# mv-scheme.net
KiCad netlist of a schematic drawn in EAGLE
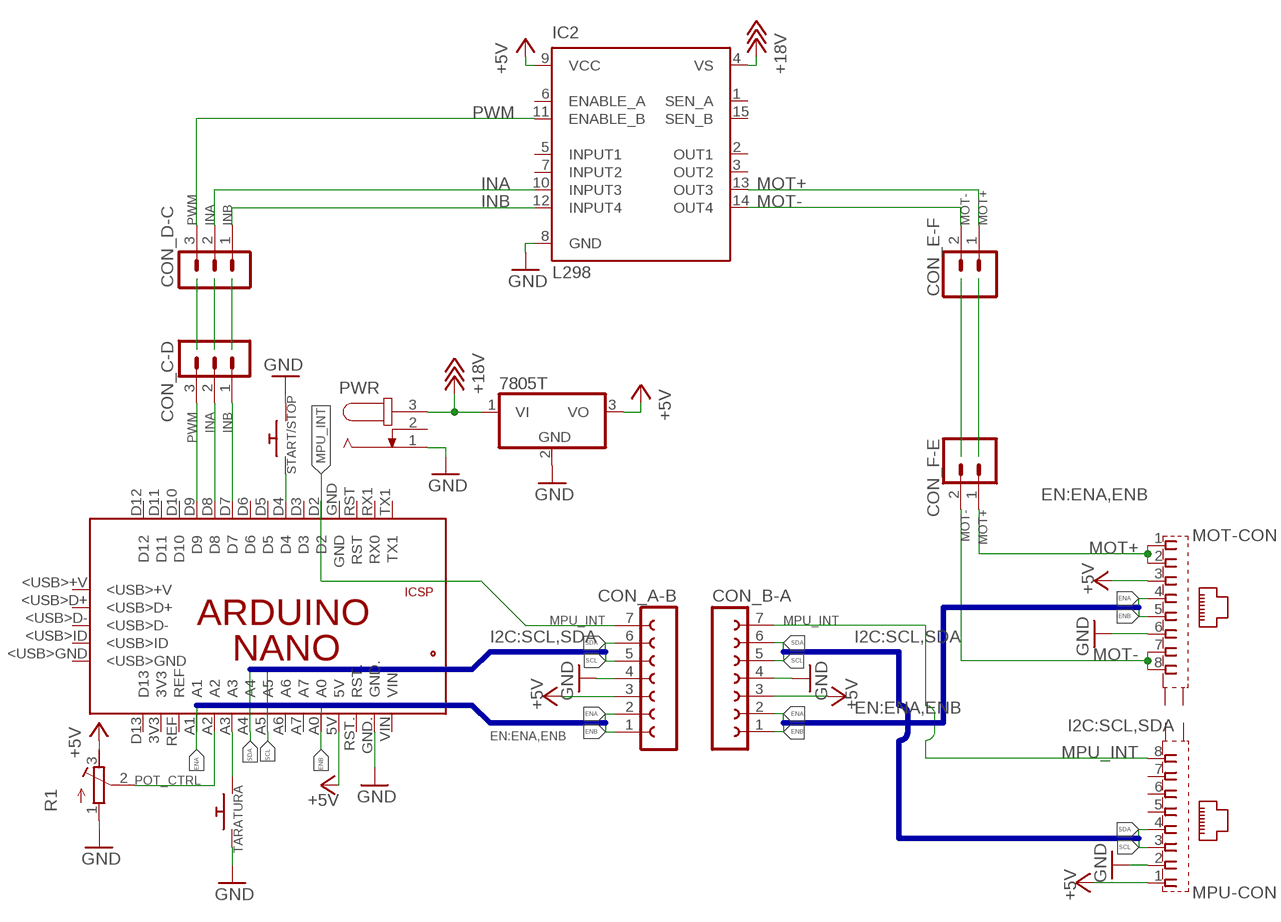
[diagram p0: schematic, sheet 1]

(export (version "E")
  (design (tool "Eeschema 10.0.6"))
  (components
    (comp (ref "CON_A-B")
      (value "FE07W")
      (footprint "eagle-import:FE07W")
      (libsource (lib "eagle-import") (part "FE07W"))
    )
    (comp (ref "CON_B-A")
      (value "FE07W")
      (footprint "eagle-import:FE07W")
      (libsource (lib "eagle-import") (part "FE07W"))
    )
    (comp (ref "CON_C-D")
      (value "MA03-1")
      (footprint "eagle-import:MA03-1")
      (libsource (lib "eagle-import") (part "MA03-1"))
    )
    (comp (ref "CON_D-C")
      (value "MA03-1")
      (footprint "eagle-import:MA03-1")
      (libsource (lib "eagle-import") (part "MA03-1"))
    )
    (comp (ref "CON_E-F")
      (value "CONN_02")
      (footprint "eagle-import:1X02")
      (libsource (lib "eagle-import") (part "CONN_02"))
    )
    (comp (ref "CON_F-E")
      (value "CONN_02")
      (footprint "eagle-import:1X02")
      (libsource (lib "eagle-import") (part "CONN_02"))
    )
    (comp (ref "IC1")
      (value "7805T")
      (footprint "eagle-import:TO220H")
      (libsource (lib "eagle-import") (part "78T05"))
    )
    (comp (ref "IC2")
      (value "L298")
      (footprint "eagle-import:MULTIWATT-15")
      (fields (field (name "MPN") "L298N"))
      (libsource (lib "eagle-import") (part "L298"))
    )
    (comp (ref "MOT-CON")
      (value "GLX-S-88M")
      (footprint "eagle-import:GLX-S-88M")
      (libsource (lib "eagle-import") (part "GLX-S-88M"))
    )
    (comp (ref "MPU-CON")
      (value "GLX-S-88M")
      (footprint "eagle-import:GLX-S-88M")
      (libsource (lib "eagle-import") (part "GLX-S-88M"))
    )
    (comp (ref "PCB1")
      (value "ARDUINO_NANO")
      (footprint "eagle-import:ARDUINO_NANO")
      (libsource (lib "eagle-import") (part "ARDUINO_NANO"))
    )
    (comp (ref "PWR")
      (value "JACK-PLUG1")
      (footprint "eagle-import:SPC4078")
      (libsource (lib "eagle-import") (part "JACK-PLUG1"))
    )
    (comp (ref "R1")
      (value "R-TRIMM64W")
      (footprint "eagle-import:RTRIM64W")
      (libsource (lib "eagle-import") (part "R-TRIMM64W"))
    )
    (comp (ref "START/STOP")
      (value "SWITCH_PUSHBUTTONEVQ-PE")
      (footprint "eagle-import:TACT_PANA-EVQ")
      (libsource (lib "eagle-import") (part "SWITCH_PUSHBUTTONEVQ-PE"))
    )
    (comp (ref "TARATURA")
      (value "SWITCH_PUSHBUTTONEVQ-PE")
      (footprint "eagle-import:TACT_PANA-EVQ")
      (libsource (lib "eagle-import") (part "SWITCH_PUSHBUTTONEVQ-PE"))
    )
  )
  (nets
    (net (code "3") (name "+5V") (class "Default")
      (node (ref "CON_A-B") (pin "3") (pinfunction "3_3") (pintype "passive"))
      (node (ref "CON_B-A") (pin "3") (pinfunction "3_3") (pintype "passive"))
      (node (ref "IC1") (pin "3") (pinfunction "VO_3") (pintype "passive"))
      (node (ref "IC2") (pin "9") (pinfunction "VCC_9") (pintype "power_in"))
      (node (ref "MOT-CON") (pin "3") (pinfunction "3_3") (pintype "passive"))
      (node (ref "MPU-CON") (pin "1") (pinfunction "1_1") (pintype "passive"))
      (node (ref "PCB1") (pin "5V") (pinfunction "5V_5V") (pintype "bidirectional"))
      (node (ref "R1") (pin "3") (pinfunction "E_3") (pintype "passive"))
    )
    (net (code "4") (name "+18V") (class "Default")
      (node (ref "IC1") (pin "1") (pinfunction "VI_1") (pintype "input"))
      (node (ref "IC2") (pin "4") (pinfunction "VS_4") (pintype "power_in"))
      (node (ref "PWR") (pin "3") (pinfunction "3_3") (pintype "passive"))
    )
    (net (code "5") (name "/INA") (class "Default")
      (node (ref "CON_C-D") (pin "2") (pinfunction "2_2") (pintype "passive"))
      (node (ref "CON_D-C") (pin "2") (pinfunction "2_2") (pintype "passive"))
      (node (ref "IC2") (pin "10") (pinfunction "INPUT3_10") (pintype "input"))
      (node (ref "PCB1") (pin "D8") (pinfunction "D8_D8") (pintype "bidirectional"))
    )
    (net (code "6") (name "/INB") (class "Default")
      (node (ref "CON_C-D") (pin "1") (pinfunction "1_1") (pintype "passive"))
      (node (ref "CON_D-C") (pin "1") (pinfunction "1_1") (pintype "passive"))
      (node (ref "IC2") (pin "12") (pinfunction "INPUT4_12") (pintype "input"))
      (node (ref "PCB1") (pin "D7") (pinfunction "D7_D7") (pintype "bidirectional"))
    )
    (net (code "7") (name "/MOT+") (class "Default")
      (node (ref "CON_E-F") (pin "1") (pinfunction "1_1") (pintype "passive"))
      (node (ref "CON_F-E") (pin "1") (pinfunction "1_1") (pintype "passive"))
      (node (ref "IC2") (pin "13") (pinfunction "OUT3_13") (pintype "output"))
      (node (ref "MOT-CON") (pin "1") (pinfunction "1_1") (pintype "passive"))
      (node (ref "MOT-CON") (pin "2") (pinfunction "2_2") (pintype "passive"))
    )
    (net (code "8") (name "/MOT-") (class "Default")
      (node (ref "CON_E-F") (pin "2") (pinfunction "2_2") (pintype "passive"))
      (node (ref "CON_F-E") (pin "2") (pinfunction "2_2") (pintype "passive"))
      (node (ref "IC2") (pin "14") (pinfunction "OUT4_14") (pintype "output"))
      (node (ref "MOT-CON") (pin "7") (pinfunction "7_7") (pintype "passive"))
      (node (ref "MOT-CON") (pin "8") (pinfunction "8_8") (pintype "passive"))
    )
    (net (code "9") (name "/POT_CTRL") (class "Default")
      (node (ref "PCB1") (pin "A2") (pinfunction "A2_A2") (pintype "bidirectional"))
      (node (ref "R1") (pin "2") (pinfunction "S_2") (pintype "passive"))
    )
    (net (code "10") (name "/PWM") (class "Default")
      (node (ref "CON_C-D") (pin "3") (pinfunction "3_3") (pintype "passive"))
      (node (ref "CON_D-C") (pin "3") (pinfunction "3_3") (pintype "passive"))
      (node (ref "IC2") (pin "11") (pinfunction "ENABLE_B_11") (pintype "input"))
      (node (ref "PCB1") (pin "D9") (pinfunction "D9_D9") (pintype "bidirectional"))
    )
    (net (code "13") (name "ENA") (class "Default")
      (node (ref "CON_A-B") (pin "2") (pinfunction "2_2") (pintype "passive"))
      (node (ref "CON_B-A") (pin "2") (pinfunction "2_2") (pintype "passive"))
      (node (ref "MOT-CON") (pin "4") (pinfunction "4_4") (pintype "passive"))
      (node (ref "PCB1") (pin "A1") (pinfunction "A1_A1") (pintype "bidirectional"))
    )
    (net (code "14") (name "ENB") (class "Default")
      (node (ref "CON_A-B") (pin "1") (pinfunction "1_1") (pintype "passive"))
      (node (ref "CON_B-A") (pin "1") (pinfunction "1_1") (pintype "passive"))
      (node (ref "MOT-CON") (pin "5") (pinfunction "5_5") (pintype "passive"))
      (node (ref "PCB1") (pin "A0") (pinfunction "A0_A0") (pintype "bidirectional"))
    )
    (net (code "15") (name "GND") (class "Default")
      (node (ref "CON_A-B") (pin "4") (pinfunction "4_4") (pintype "passive"))
      (node (ref "CON_B-A") (pin "4") (pinfunction "4_4") (pintype "passive"))
      (node (ref "IC1") (pin "2") (pinfunction "GND_2") (pintype "passive"))
      (node (ref "IC2") (pin "8") (pinfunction "GND_8") (pintype "power_in"))
      (node (ref "MOT-CON") (pin "6") (pinfunction "6_6") (pintype "passive"))
      (node (ref "MPU-CON") (pin "2") (pinfunction "2_2") (pintype "passive"))
      (node (ref "PCB1") (pin "GND.") (pinfunction "GND._GND.") (pintype "bidirectional"))
      (node (ref "PWR") (pin "1") (pinfunction "1_1") (pintype "passive"))
      (node (ref "R1") (pin "1") (pinfunction "A_1") (pintype "passive"))
      (node (ref "START/STOP") (pin "P$2") (pinfunction "P$2_P$2") (pintype "passive"))
      (node (ref "TARATURA") (pin "P$2") (pinfunction "P$2_P$2") (pintype "passive"))
    )
    (net (code "16") (name "MPU_INT") (class "Default")
      (node (ref "CON_A-B") (pin "7") (pinfunction "7_7") (pintype "passive"))
      (node (ref "CON_B-A") (pin "7") (pinfunction "7_7") (pintype "passive"))
      (node (ref "MPU-CON") (pin "8") (pinfunction "8_8") (pintype "passive"))
      (node (ref "PCB1") (pin "D2") (pinfunction "D2_D2") (pintype "bidirectional"))
    )
    (net (code "17") (name "Net-(PCB1-PadA3)") (class "Default")
      (node (ref "PCB1") (pin "A3") (pinfunction "A3_A3") (pintype "bidirectional"))
      (node (ref "TARATURA") (pin "P$1") (pinfunction "P$1_P$1") (pintype "passive"))
    )
    (net (code "18") (name "Net-(PCB1-PadD4)") (class "Default")
      (node (ref "PCB1") (pin "D4") (pinfunction "D4_D4") (pintype "bidirectional"))
      (node (ref "START/STOP") (pin "P$1") (pinfunction "P$1_P$1") (pintype "passive"))
    )
    (net (code "19") (name "SCL") (class "Default")
      (node (ref "CON_A-B") (pin "5") (pinfunction "5_5") (pintype "passive"))
      (node (ref "CON_B-A") (pin "5") (pinfunction "5_5") (pintype "passive"))
      (node (ref "MPU-CON") (pin "3") (pinfunction "3_3") (pintype "passive"))
      (node (ref "PCB1") (pin "A5") (pinfunction "A5_A5") (pintype "bidirectional"))
    )
    (net (code "20") (name "SDA") (class "Default")
      (node (ref "CON_A-B") (pin "6") (pinfunction "6_6") (pintype "passive"))
      (node (ref "CON_B-A") (pin "6") (pinfunction "6_6") (pintype "passive"))
      (node (ref "MPU-CON") (pin "4") (pinfunction "4_4") (pintype "passive"))
      (node (ref "PCB1") (pin "A4") (pinfunction "A4_A4") (pintype "bidirectional"))
    )
    (net (code "21") (name "unconnected-(IC2-ENABLE_A-Pad6)") (class "Default")
      (node (ref "IC2") (pin "6") (pinfunction "ENABLE_A_6") (pintype "input"))
    )
    (net (code "22") (name "unconnected-(IC2-INPUT1-Pad5)") (class "Default")
      (node (ref "IC2") (pin "5") (pinfunction "INPUT1_5") (pintype "input"))
    )
    (net (code "23") (name "unconnected-(IC2-INPUT2-Pad7)") (class "Default")
      (node (ref "IC2") (pin "7") (pinfunction "INPUT2_7") (pintype "input"))
    )
    (net (code "24") (name "unconnected-(IC2-OUT1-Pad2)") (class "Default")
      (node (ref "IC2") (pin "2") (pinfunction "OUT1_2") (pintype "output"))
    )
    (net (code "25") (name "unconnected-(IC2-OUT2-Pad3)") (class "Default")
      (node (ref "IC2") (pin "3") (pinfunction "OUT2_3") (pintype "output"))
    )
    (net (code "26") (name "unconnected-(IC2-SEN_A-Pad1)") (class "Default")
      (node (ref "IC2") (pin "1") (pinfunction "SEN_A_1") (pintype "input"))
    )
    (net (code "27") (name "unconnected-(IC2-SEN_B-Pad15)") (class "Default")
      (node (ref "IC2") (pin "15") (pinfunction "SEN_B_15") (pintype "input"))
    )
    (net (code "28") (name "unconnected-(MOT-CON-PadS1)") (class "Default")
      (node (ref "MOT-CON") (pin "S1") (pinfunction "S1_S1") (pintype "passive"))
    )
    (net (code "29") (name "unconnected-(MOT-CON-PadS2)") (class "Default")
      (node (ref "MOT-CON") (pin "S2") (pinfunction "S2_S2") (pintype "passive"))
    )
    (net (code "30") (name "unconnected-(MPU-CON-Pad5)") (class "Default")
      (node (ref "MPU-CON") (pin "5") (pinfunction "5_5") (pintype "passive"))
    )
    (net (code "31") (name "unconnected-(MPU-CON-Pad6)") (class "Default")
      (node (ref "MPU-CON") (pin "6") (pinfunction "6_6") (pintype "passive"))
    )
    (net (code "32") (name "unconnected-(MPU-CON-Pad7)") (class "Default")
      (node (ref "MPU-CON") (pin "7") (pinfunction "7_7") (pintype "passive"))
    )
    (net (code "33") (name "unconnected-(MPU-CON-PadS1)") (class "Default")
      (node (ref "MPU-CON") (pin "S1") (pinfunction "S1_S1") (pintype "passive"))
    )
    (net (code "34") (name "unconnected-(MPU-CON-PadS2)") (class "Default")
      (node (ref "MPU-CON") (pin "S2") (pinfunction "S2_S2") (pintype "passive"))
    )
    (net (code "35") (name "unconnected-(PCB1-Pad3V3)") (class "Default")
      (node (ref "PCB1") (pin "3V3") (pinfunction "3V3_3V3") (pintype "bidirectional"))
    )
    (net (code "36") (name "unconnected-(PCB1-Pad5V.)") (class "Default")
      (node (ref "PCB1") (pin "5V.") (pinfunction "5V._5V.") (pintype "bidirectional"))
    )
    (net (code "37") (name "unconnected-(PCB1-Pad<USB>+V)") (class "Default")
      (node (ref "PCB1") (pin "<USB>+V") (pinfunction "<USB>+V_<USB>+V") (pintype "bidirectional"))
    )
    (net (code "38") (name "unconnected-(PCB1-Pad<USB>D+)") (class "Default")
      (node (ref "PCB1") (pin "<USB>D+") (pinfunction "<USB>D+_<USB>D+") (pintype "bidirectional"))
    )
    (net (code "39") (name "unconnected-(PCB1-Pad<USB>D-)") (class "Default")
      (node (ref "PCB1") (pin "<USB>D-") (pinfunction "<USB>D-_<USB>D-") (pintype "bidirectional"))
    )
    (net (code "40") (name "unconnected-(PCB1-Pad<USB>GND)") (class "Default")
      (node (ref "PCB1") (pin "<USB>GND") (pinfunction "<USB>GND_<USB>GND") (pintype "bidirectional"))
    )
    (net (code "41") (name "unconnected-(PCB1-Pad<USB>ID)") (class "Default")
      (node (ref "PCB1") (pin "<USB>ID") (pinfunction "<USB>ID_<USB>ID") (pintype "bidirectional"))
    )
    (net (code "42") (name "unconnected-(PCB1-PadA6)") (class "Default")
      (node (ref "PCB1") (pin "A6") (pinfunction "A6_A6") (pintype "bidirectional"))
    )
    (net (code "43") (name "unconnected-(PCB1-PadA7)") (class "Default")
      (node (ref "PCB1") (pin "A7") (pinfunction "A7_A7") (pintype "bidirectional"))
    )
    (net (code "44") (name "unconnected-(PCB1-PadD3)") (class "Default")
      (node (ref "PCB1") (pin "D3") (pinfunction "D3_D3") (pintype "bidirectional"))
    )
    (net (code "45") (name "unconnected-(PCB1-PadD5)") (class "Default")
      (node (ref "PCB1") (pin "D5") (pinfunction "D5_D5") (pintype "bidirectional"))
    )
    (net (code "46") (name "unconnected-(PCB1-PadD6)") (class "Default")
      (node (ref "PCB1") (pin "D6") (pinfunction "D6_D6") (pintype "bidirectional"))
    )
    (net (code "47") (name "unconnected-(PCB1-PadD10)") (class "Default")
      (node (ref "PCB1") (pin "D10") (pinfunction "D10_D10") (pintype "bidirectional"))
    )
    (net (code "48") (name "unconnected-(PCB1-PadD11)") (class "Default")
      (node (ref "PCB1") (pin "D11") (pinfunction "D11_D11") (pintype "bidirectional"))
    )
    (net (code "49") (name "unconnected-(PCB1-PadD12)") (class "Default")
      (node (ref "PCB1") (pin "D12") (pinfunction "D12_D12") (pintype "bidirectional"))
    )
    (net (code "50") (name "unconnected-(PCB1-PadD13)") (class "Default")
      (node (ref "PCB1") (pin "D13") (pinfunction "D13_D13") (pintype "bidirectional"))
    )
    (net (code "51") (name "unconnected-(PCB1-PadGND)") (class "Default")
      (node (ref "PCB1") (pin "GND") (pinfunction "GND_GND") (pintype "bidirectional"))
    )
    (net (code "52") (name "unconnected-(PCB1-PadGND_)") (class "Default")
      (node (ref "PCB1") (pin "GND_") (pinfunction "GND__GND_") (pintype "bidirectional"))
    )
    (net (code "53") (name "unconnected-(PCB1-PadMISO)") (class "Default")
      (node (ref "PCB1") (pin "MISO") (pinfunction "MISO_MISO") (pintype "bidirectional"))
    )
    (net (code "54") (name "unconnected-(PCB1-PadMOSI)") (class "Default")
      (node (ref "PCB1") (pin "MOSI") (pinfunction "MOSI_MOSI") (pintype "bidirectional"))
    )
    (net (code "55") (name "unconnected-(PCB1-PadREF)") (class "Default")
      (node (ref "PCB1") (pin "REF") (pinfunction "REF_REF") (pintype "bidirectional"))
    )
    (net (code "56") (name "unconnected-(PCB1-PadRESET..)") (class "Default")
      (node (ref "PCB1") (pin "RESET..") (pinfunction "RESET.._RESET..") (pintype "bidirectional"))
    )
    (net (code "57") (name "unconnected-(PCB1-PadRST)") (class "Default")
      (node (ref "PCB1") (pin "RST") (pinfunction "RST_RST") (pintype "bidirectional"))
    )
    (net (code "58") (name "unconnected-(PCB1-PadRST.)") (class "Default")
      (node (ref "PCB1") (pin "RST.") (pinfunction "RST._RST.") (pintype "bidirectional"))
    )
    (net (code "59") (name "unconnected-(PCB1-PadSCK)") (class "Default")
      (node (ref "PCB1") (pin "SCK") (pinfunction "SCK_SCK") (pintype "bidirectional"))
    )
    (net (code "60") (name "unconnected-(PCB1-PadTX1)") (class "Default")
      (node (ref "PCB1") (pin "TX1") (pinfunction "TX1_TX1") (pintype "bidirectional"))
    )
    (net (code "61") (name "unconnected-(PCB1-PadVIN)") (class "Default")
      (node (ref "PCB1") (pin "VIN") (pinfunction "VIN_VIN") (pintype "bidirectional"))
    )
    (net (code "62") (name "unconnected-(PCB1-RX0-PadRX1)") (class "Default")
      (node (ref "PCB1") (pin "RX1") (pinfunction "RX0_RX1") (pintype "bidirectional"))
    )
    (net (code "63") (name "unconnected-(PWR-Pad2)") (class "Default")
      (node (ref "PWR") (pin "2") (pinfunction "2_2") (pintype "passive"))
    )
  )
)
